# RoomIndicator_old.net
KiCad netlist of a schematic drawn in EAGLE
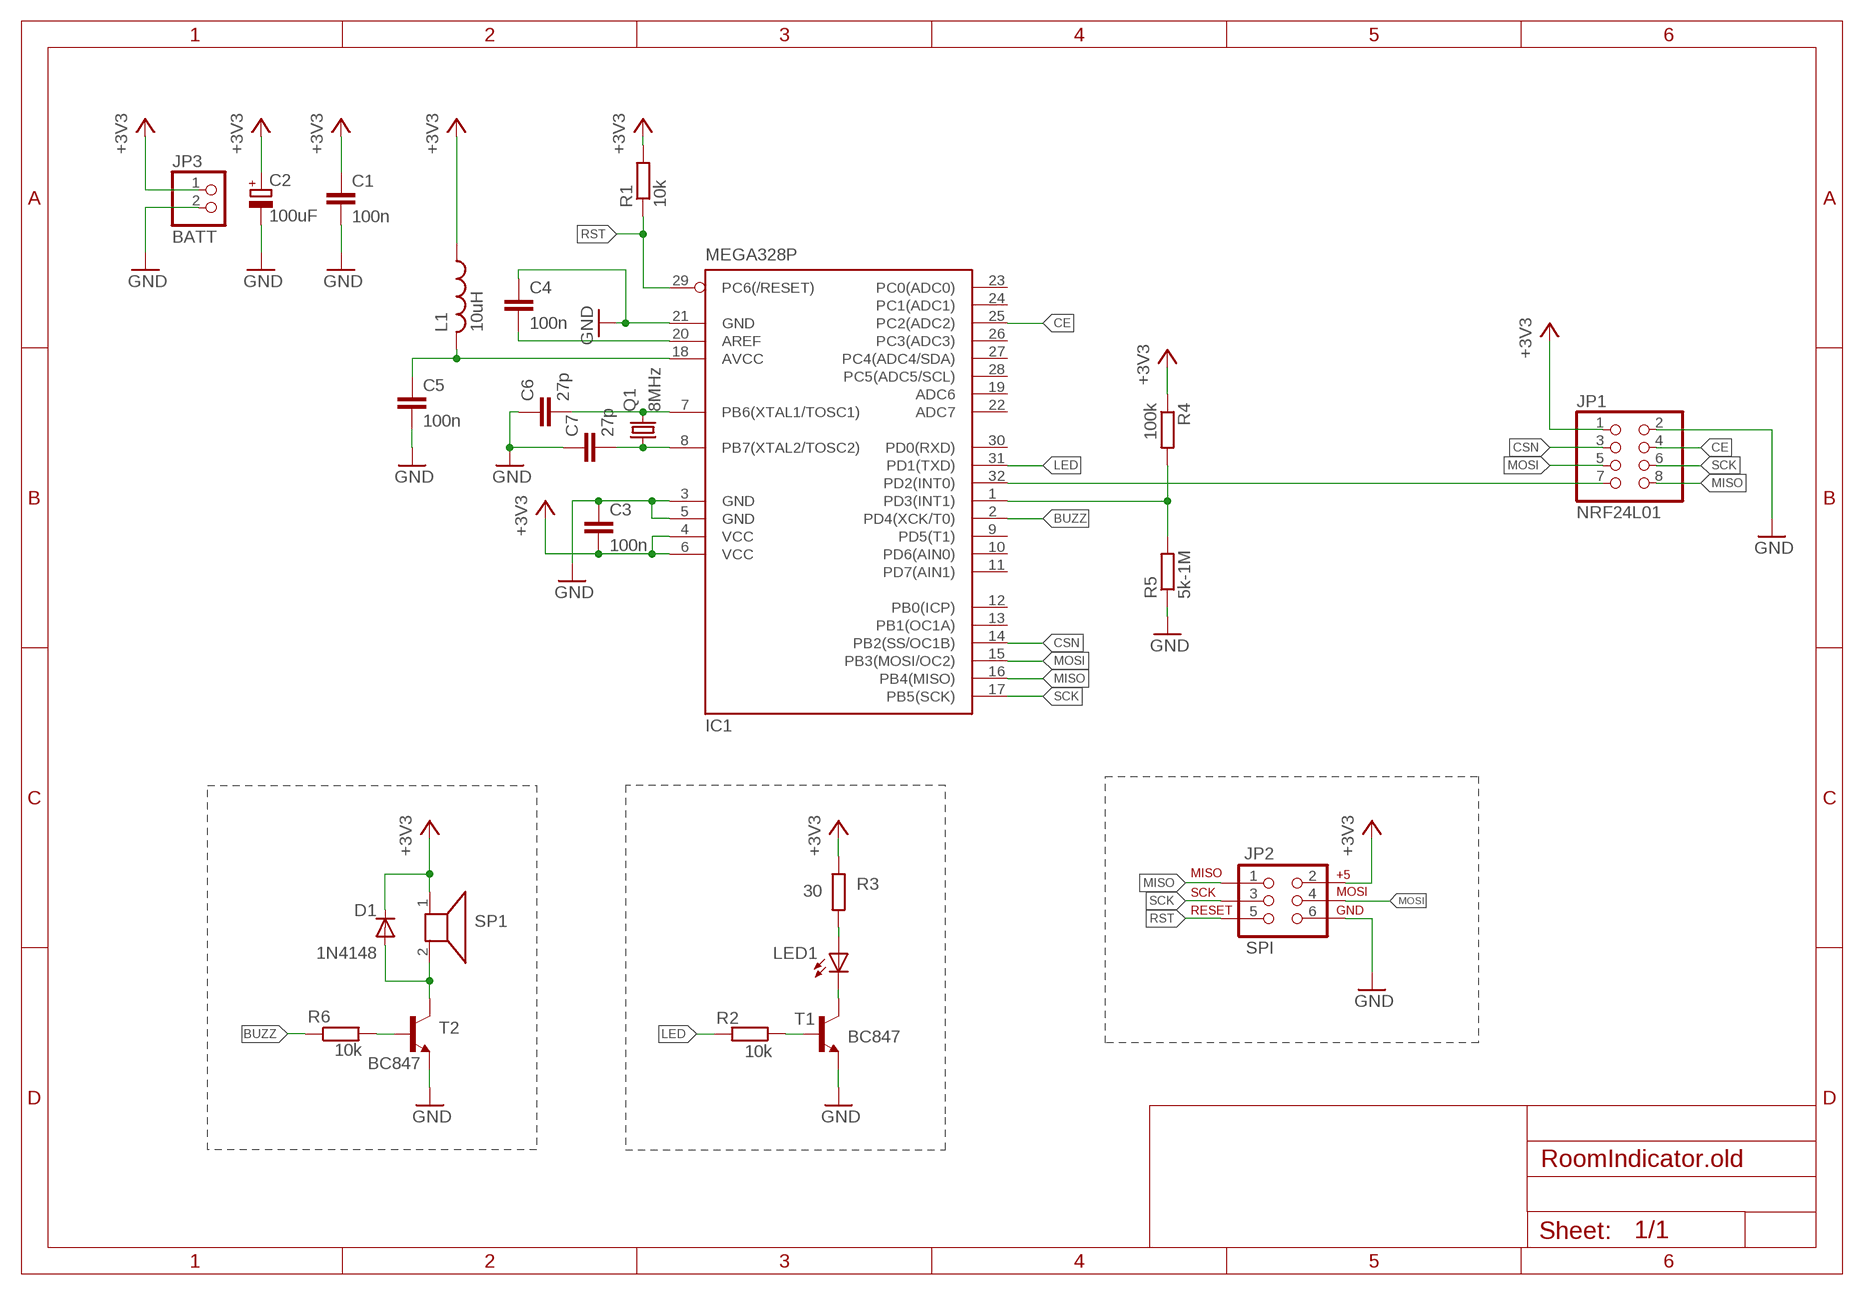
[diagram p0: schematic, sheet 1]

(export (version "E")
  (design (tool "Eeschema 10.0.6"))
  (components
    (comp (ref "C1")
      (value "100n")
      (footprint "eagle-import:C025-025X050")
      (libsource (lib "eagle-import") (part "C-EU025-025X050"))
    )
    (comp (ref "C2")
      (value "100uF")
      (footprint "eagle-import:E2,5-5")
      (libsource (lib "eagle-import") (part "CPOL-EUE2.5-5"))
    )
    (comp (ref "C3")
      (value "100n")
      (footprint "eagle-import:C0805K")
      (libsource (lib "eagle-import") (part "C-EUC0805K"))
    )
    (comp (ref "C4")
      (value "100n")
      (footprint "eagle-import:C0805K")
      (libsource (lib "eagle-import") (part "C-EUC0805K"))
    )
    (comp (ref "C5")
      (value "100n")
      (footprint "eagle-import:C0805K")
      (libsource (lib "eagle-import") (part "C-EUC0805K"))
    )
    (comp (ref "C6")
      (value "27p")
      (footprint "eagle-import:C0805K")
      (libsource (lib "eagle-import") (part "C-EUC0805K"))
    )
    (comp (ref "C7")
      (value "27p")
      (footprint "eagle-import:C0805K")
      (libsource (lib "eagle-import") (part "C-EUC0805K"))
    )
    (comp (ref "D1")
      (value "1N4148")
      (footprint "eagle-import:DO35-7")
      (libsource (lib "eagle-import") (part "1N4148DO35-7"))
    )
    (comp (ref "IC1")
      (value "MEGA328P")
      (footprint "eagle-import:TQFP32-08")
      (fields (field (name "MPN") "ATMEGA8-16AU"))
      (libsource (lib "eagle-import") (part "MEGA8-AI"))
    )
    (comp (ref "JP1")
      (value "NRF24L01")
      (footprint "eagle-import:2X04")
      (libsource (lib "eagle-import") (part "PINHD-2X4"))
    )
    (comp (ref "JP2")
      (value "SPI")
      (footprint "eagle-import:2X3")
      (libsource (lib "eagle-import") (part "AVR_SPI_PRG_6PTH"))
    )
    (comp (ref "JP3")
      (value "BATT")
      (footprint "eagle-import:1X02")
      (libsource (lib "eagle-import") (part "PINHD-1X2"))
    )
    (comp (ref "L1")
      (value "10uH")
      (footprint "eagle-import:0204_7")
      (libsource (lib "eagle-import") (part "L-US0204/7"))
    )
    (comp (ref "LED1")
      (value "GREEN")
      (footprint "eagle-import:LED5MM")
      (libsource (lib "eagle-import") (part "LED5MM"))
    )
    (comp (ref "Q1")
      (value "8MHz")
      (footprint "eagle-import:HC49_S")
      (libsource (lib "eagle-import") (part "CRYSTALHC49S"))
    )
    (comp (ref "R1")
      (value "10k")
      (footprint "eagle-import:R0805")
      (libsource (lib "eagle-import") (part "R-EU_R0805"))
    )
    (comp (ref "R2")
      (value "10k")
      (footprint "eagle-import:R0805")
      (libsource (lib "eagle-import") (part "R-EU_R0805"))
    )
    (comp (ref "R3")
      (value "30")
      (footprint "eagle-import:0204_5")
      (libsource (lib "eagle-import") (part "R-EU_0204/5"))
    )
    (comp (ref "R4")
      (value "100k")
      (footprint "eagle-import:R0805")
      (libsource (lib "eagle-import") (part "R-EU_R0805"))
    )
    (comp (ref "R5")
      (value "5k-1M")
      (footprint "eagle-import:0204_5")
      (libsource (lib "eagle-import") (part "R-EU_0204/5"))
    )
    (comp (ref "R6")
      (value "10k")
      (footprint "eagle-import:R0805")
      (libsource (lib "eagle-import") (part "R-EU_R0805"))
    )
    (comp (ref "SP1")
      (value "AL60P")
      (footprint "eagle-import:AL60P")
      (libsource (lib "eagle-import") (part "AL60P"))
    )
    (comp (ref "T1")
      (value "BC847")
      (footprint "eagle-import:SOT23")
      (libsource (lib "eagle-import") (part "BC847"))
    )
    (comp (ref "T2")
      (value "BC847")
      (footprint "eagle-import:SOT23")
      (libsource (lib "eagle-import") (part "BC847"))
    )
  )
  (nets
    (net (code "1") (name "+3V3") (class "Default")
      (node (ref "C1") (pin "1") (pinfunction "1_1") (pintype "passive"))
      (node (ref "C2") (pin "+") (pinfunction "+_+") (pintype "passive"))
      (node (ref "C3") (pin "2") (pinfunction "2_2") (pintype "passive"))
      (node (ref "D1") (pin "C") (pinfunction "C_C") (pintype "passive"))
      (node (ref "IC1") (pin "4") (pinfunction "VCC_4") (pintype "power_in"))
      (node (ref "IC1") (pin "6") (pinfunction "VCC_6") (pintype "power_in"))
      (node (ref "JP1") (pin "1") (pinfunction "1_1") (pintype "passive"))
      (node (ref "JP2") (pin "2") (pinfunction "2_2") (pintype "passive"))
      (node (ref "JP3") (pin "1") (pinfunction "1_1") (pintype "passive"))
      (node (ref "L1") (pin "1") (pinfunction "1_1") (pintype "passive"))
      (node (ref "R1") (pin "2") (pinfunction "2_2") (pintype "passive"))
      (node (ref "R3") (pin "1") (pinfunction "1_1") (pintype "passive"))
      (node (ref "R4") (pin "1") (pinfunction "1_1") (pintype "passive"))
      (node (ref "SP1") (pin "1") (pinfunction "1_1") (pintype "passive"))
    )
    (net (code "2") (name "BUZZ") (class "Default")
      (node (ref "IC1") (pin "2") (pinfunction "PD4(XCK/T0)_2") (pintype "bidirectional"))
      (node (ref "R6") (pin "1") (pinfunction "1_1") (pintype "passive"))
    )
    (net (code "3") (name "CE") (class "Default")
      (node (ref "IC1") (pin "25") (pinfunction "PC2(ADC2)_25") (pintype "bidirectional"))
      (node (ref "JP1") (pin "4") (pinfunction "4_4") (pintype "passive"))
    )
    (net (code "4") (name "CSN") (class "Default")
      (node (ref "IC1") (pin "14") (pinfunction "PB2(SS/OC1B)_14") (pintype "bidirectional"))
      (node (ref "JP1") (pin "3") (pinfunction "3_3") (pintype "passive"))
    )
    (net (code "5") (name "GND") (class "Default")
      (node (ref "C1") (pin "2") (pinfunction "2_2") (pintype "passive"))
      (node (ref "C2") (pin "-") (pinfunction "-_-") (pintype "passive"))
      (node (ref "C3") (pin "1") (pinfunction "1_1") (pintype "passive"))
      (node (ref "C4") (pin "1") (pinfunction "1_1") (pintype "passive"))
      (node (ref "C5") (pin "2") (pinfunction "2_2") (pintype "passive"))
      (node (ref "C6") (pin "1") (pinfunction "1_1") (pintype "passive"))
      (node (ref "C7") (pin "1") (pinfunction "1_1") (pintype "passive"))
      (node (ref "IC1") (pin "21") (pinfunction "GND_21") (pintype "power_in"))
      (node (ref "IC1") (pin "3") (pinfunction "GND_3") (pintype "power_in"))
      (node (ref "IC1") (pin "5") (pinfunction "GND_5") (pintype "power_in"))
      (node (ref "JP1") (pin "2") (pinfunction "2_2") (pintype "passive"))
      (node (ref "JP2") (pin "6") (pinfunction "6_6") (pintype "passive"))
      (node (ref "JP3") (pin "2") (pinfunction "2_2") (pintype "passive"))
      (node (ref "R5") (pin "1") (pinfunction "1_1") (pintype "passive"))
      (node (ref "T1") (pin "2") (pinfunction "E_2") (pintype "passive"))
      (node (ref "T2") (pin "2") (pinfunction "E_2") (pintype "passive"))
    )
    (net (code "6") (name "LED") (class "Default")
      (node (ref "IC1") (pin "31") (pinfunction "PD1(TXD)_31") (pintype "bidirectional"))
      (node (ref "R2") (pin "2") (pinfunction "2_2") (pintype "passive"))
    )
    (net (code "7") (name "MISO") (class "Default")
      (node (ref "IC1") (pin "16") (pinfunction "PB4(MISO)_16") (pintype "bidirectional"))
      (node (ref "JP1") (pin "8") (pinfunction "8_8") (pintype "passive"))
      (node (ref "JP2") (pin "1") (pinfunction "1_1") (pintype "passive"))
    )
    (net (code "8") (name "MOSI") (class "Default")
      (node (ref "IC1") (pin "15") (pinfunction "PB3(MOSI/OC2)_15") (pintype "bidirectional"))
      (node (ref "JP1") (pin "5") (pinfunction "5_5") (pintype "passive"))
      (node (ref "JP2") (pin "4") (pinfunction "4_4") (pintype "passive"))
    )
    (net (code "9") (name "Net-(IC1-AREF)") (class "Default")
      (node (ref "C4") (pin "2") (pinfunction "2_2") (pintype "passive"))
      (node (ref "IC1") (pin "20") (pinfunction "AREF_20") (pintype "passive"))
    )
    (net (code "10") (name "Net-(IC1-AVCC)") (class "Default")
      (node (ref "C5") (pin "1") (pinfunction "1_1") (pintype "passive"))
      (node (ref "IC1") (pin "18") (pinfunction "AVCC_18") (pintype "power_in"))
      (node (ref "L1") (pin "2") (pinfunction "2_2") (pintype "passive"))
    )
    (net (code "11") (name "Net-(IC1-PB6(XTAL1{slash}TOSC1))") (class "Default")
      (node (ref "C6") (pin "2") (pinfunction "2_2") (pintype "passive"))
      (node (ref "IC1") (pin "7") (pinfunction "PB6(XTAL1/TOSC1)_7") (pintype "bidirectional"))
      (node (ref "Q1") (pin "2") (pinfunction "2_2") (pintype "passive"))
    )
    (net (code "12") (name "Net-(IC1-PB7(XTAL2{slash}TOSC2))") (class "Default")
      (node (ref "C7") (pin "2") (pinfunction "2_2") (pintype "passive"))
      (node (ref "IC1") (pin "8") (pinfunction "PB7(XTAL2/TOSC2)_8") (pintype "bidirectional"))
      (node (ref "Q1") (pin "1") (pinfunction "1_1") (pintype "passive"))
    )
    (net (code "13") (name "Net-(IC1-PD2(INT0))") (class "Default")
      (node (ref "IC1") (pin "32") (pinfunction "PD2(INT0)_32") (pintype "bidirectional"))
      (node (ref "JP1") (pin "7") (pinfunction "7_7") (pintype "passive"))
    )
    (net (code "14") (name "Net-(IC1-PD3(INT1))") (class "Default")
      (node (ref "IC1") (pin "1") (pinfunction "PD3(INT1)_1") (pintype "bidirectional"))
      (node (ref "R4") (pin "2") (pinfunction "2_2") (pintype "passive"))
      (node (ref "R5") (pin "2") (pinfunction "2_2") (pintype "passive"))
    )
    (net (code "15") (name "Net-(LED1-C)") (class "Default")
      (node (ref "LED1") (pin "K") (pinfunction "C_K") (pintype "passive"))
      (node (ref "T1") (pin "3") (pinfunction "C_3") (pintype "passive"))
    )
    (net (code "16") (name "Net-(LED1-PadA)") (class "Default")
      (node (ref "LED1") (pin "A") (pinfunction "A_A") (pintype "passive"))
      (node (ref "R3") (pin "2") (pinfunction "2_2") (pintype "passive"))
    )
    (net (code "17") (name "Net-(T1-B)") (class "Default")
      (node (ref "R2") (pin "1") (pinfunction "1_1") (pintype "passive"))
      (node (ref "T1") (pin "1") (pinfunction "B_1") (pintype "passive"))
    )
    (net (code "18") (name "Net-(T2-B)") (class "Default")
      (node (ref "R6") (pin "2") (pinfunction "2_2") (pintype "passive"))
      (node (ref "T2") (pin "1") (pinfunction "B_1") (pintype "passive"))
    )
    (net (code "19") (name "Net-(T2-C)") (class "Default")
      (node (ref "D1") (pin "A") (pinfunction "A_A") (pintype "passive"))
      (node (ref "SP1") (pin "2") (pinfunction "2_2") (pintype "passive"))
      (node (ref "T2") (pin "3") (pinfunction "C_3") (pintype "passive"))
    )
    (net (code "20") (name "RST") (class "Default")
      (node (ref "IC1") (pin "29") (pinfunction "PC6(/RESET)_29") (pintype "bidirectional"))
      (node (ref "JP2") (pin "5") (pinfunction "5_5") (pintype "passive"))
      (node (ref "R1") (pin "1") (pinfunction "1_1") (pintype "passive"))
    )
    (net (code "21") (name "SCK") (class "Default")
      (node (ref "IC1") (pin "17") (pinfunction "PB5(SCK)_17") (pintype "bidirectional"))
      (node (ref "JP1") (pin "6") (pinfunction "6_6") (pintype "passive"))
      (node (ref "JP2") (pin "3") (pinfunction "3_3") (pintype "passive"))
    )
    (net (code "22") (name "unconnected-(IC1-ADC6-Pad19)") (class "Default")
      (node (ref "IC1") (pin "19") (pinfunction "ADC6_19") (pintype "bidirectional"))
    )
    (net (code "23") (name "unconnected-(IC1-ADC7-Pad22)") (class "Default")
      (node (ref "IC1") (pin "22") (pinfunction "ADC7_22") (pintype "bidirectional"))
    )
    (net (code "24") (name "unconnected-(IC1-PB0(ICP)-Pad12)") (class "Default")
      (node (ref "IC1") (pin "12") (pinfunction "PB0(ICP)_12") (pintype "bidirectional"))
    )
    (net (code "25") (name "unconnected-(IC1-PB1(OC1A)-Pad13)") (class "Default")
      (node (ref "IC1") (pin "13") (pinfunction "PB1(OC1A)_13") (pintype "bidirectional"))
    )
    (net (code "26") (name "unconnected-(IC1-PC0(ADC0)-Pad23)") (class "Default")
      (node (ref "IC1") (pin "23") (pinfunction "PC0(ADC0)_23") (pintype "bidirectional"))
    )
    (net (code "27") (name "unconnected-(IC1-PC1(ADC1)-Pad24)") (class "Default")
      (node (ref "IC1") (pin "24") (pinfunction "PC1(ADC1)_24") (pintype "bidirectional"))
    )
    (net (code "28") (name "unconnected-(IC1-PC3(ADC3)-Pad26)") (class "Default")
      (node (ref "IC1") (pin "26") (pinfunction "PC3(ADC3)_26") (pintype "bidirectional"))
    )
    (net (code "29") (name "unconnected-(IC1-PC4(ADC4{slash}SDA)-Pad27)") (class "Default")
      (node (ref "IC1") (pin "27") (pinfunction "PC4(ADC4/SDA)_27") (pintype "bidirectional"))
    )
    (net (code "30") (name "unconnected-(IC1-PC5(ADC5{slash}SCL)-Pad28)") (class "Default")
      (node (ref "IC1") (pin "28") (pinfunction "PC5(ADC5/SCL)_28") (pintype "bidirectional"))
    )
    (net (code "31") (name "unconnected-(IC1-PD0(RXD)-Pad30)") (class "Default")
      (node (ref "IC1") (pin "30") (pinfunction "PD0(RXD)_30") (pintype "bidirectional"))
    )
    (net (code "32") (name "unconnected-(IC1-PD5(T1)-Pad9)") (class "Default")
      (node (ref "IC1") (pin "9") (pinfunction "PD5(T1)_9") (pintype "bidirectional"))
    )
    (net (code "33") (name "unconnected-(IC1-PD6(AIN0)-Pad10)") (class "Default")
      (node (ref "IC1") (pin "10") (pinfunction "PD6(AIN0)_10") (pintype "bidirectional"))
    )
    (net (code "34") (name "unconnected-(IC1-PD7(AIN1)-Pad11)") (class "Default")
      (node (ref "IC1") (pin "11") (pinfunction "PD7(AIN1)_11") (pintype "bidirectional"))
    )
  )
)
